# 555-PWM-Motor-Speed-Controller.net
KiCad netlist of a schematic drawn in EAGLE
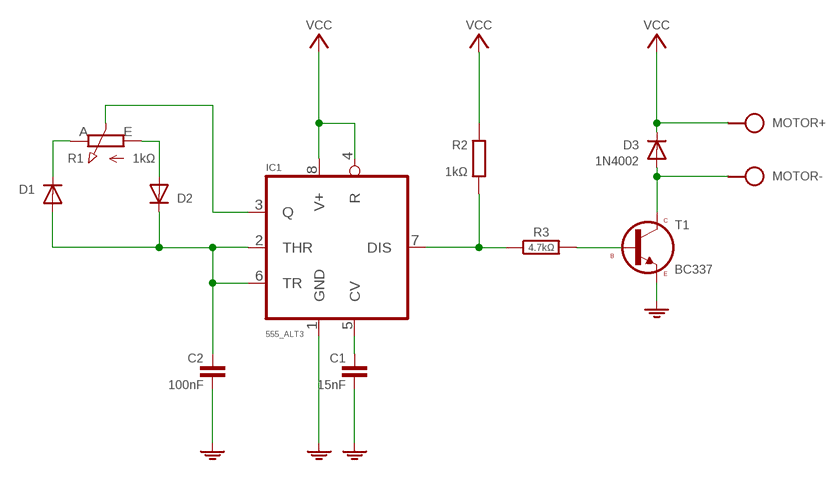
[diagram p0: schematic, sheet 1]

(export (version "E")
  (design (tool "Eeschema 10.0.6"))
  (components
    (comp (ref "C1")
      (value "15nF")
      (footprint "eagle-import:C050-020X044_V")
      (libsource (lib "eagle-import") (part "C050-020X044/V"))
    )
    (comp (ref "C2")
      (value "100nF")
      (footprint "eagle-import:C075-020X044")
      (libsource (lib "eagle-import") (part "C075-020X044"))
    )
    (comp (ref "D1")
      (value "DIODE34-7V")
      (footprint "eagle-import:DO34-7V")
      (libsource (lib "eagle-import") (part "DIODE34-7V"))
    )
    (comp (ref "D2")
      (value "DIODE34-7V")
      (footprint "eagle-import:DO34-7V")
      (libsource (lib "eagle-import") (part "DIODE34-7V"))
    )
    (comp (ref "D3")
      (value "1N4002")
      (footprint "eagle-import:DO35-7")
      (libsource (lib "eagle-import") (part "DIODE35-7"))
    )
    (comp (ref "IC1")
      (value "555_ALT3")
      (footprint "eagle-import:DIL08")
      (libsource (lib "eagle-import") (part "555_ALT3"))
    )
    (comp (ref "MOTOR")
      (value "SPAD+-+-")
      (footprint "eagle-import:SPAD+-")
      (libsource (lib "eagle-import") (part "SPAD+-+-"))
    )
    (comp (ref "R1")
      (value "1kΩ")
      (footprint "eagle-import:CONN-3P")
      (libsource (lib "eagle-import") (part "POT-H-3P"))
    )
    (comp (ref "R2")
      (value "1kΩ")
      (footprint "eagle-import:0204_10")
      (libsource (lib "eagle-import") (part "R0204/10"))
    )
    (comp (ref "R3")
      (value "4.7kΩ")
      (footprint "eagle-import:0204_10")
      (libsource (lib "eagle-import") (part "R-H0204/10"))
    )
    (comp (ref "S1")
      (value "VCC_GNDL")
      (footprint "eagle-import:SPAD-+")
      (libsource (lib "eagle-import") (part "VCC_GNDL"))
    )
    (comp (ref "T1")
      (value "BC337")
      (footprint "eagle-import:TO92-CBE-A")
      (libsource (lib "eagle-import") (part "BC337CBE-A"))
    )
  )
  (nets
    (net (code "1") (name "GND") (class "Default")
      (node (ref "C1") (pin "2") (pinfunction "2_2") (pintype "passive"))
      (node (ref "C2") (pin "2") (pinfunction "2_2") (pintype "passive"))
      (node (ref "IC1") (pin "1") (pinfunction "GND_1") (pintype "power_in"))
      (node (ref "S1") (pin "1") (pinfunction "GND_1") (pintype "power_in"))
      (node (ref "T1") (pin "3") (pinfunction "E_3") (pintype "passive"))
    )
    (net (code "2") (name "Net-(IC1-CV)") (class "Default")
      (node (ref "C1") (pin "1") (pinfunction "1_1") (pintype "passive"))
      (node (ref "IC1") (pin "5") (pinfunction "CV_5") (pintype "input"))
    )
    (net (code "3") (name "Net-(IC1-DIS)") (class "Default")
      (node (ref "IC1") (pin "7") (pinfunction "DIS_7") (pintype "passive"))
      (node (ref "R2") (pin "2") (pinfunction "1_2") (pintype "passive"))
      (node (ref "R3") (pin "1") (pinfunction "1_1") (pintype "passive"))
    )
    (net (code "4") (name "Net-(IC1-Q)") (class "Default")
      (node (ref "IC1") (pin "3") (pinfunction "Q_3") (pintype "output"))
      (node (ref "R1") (pin "2") (pinfunction "S_2") (pintype "passive"))
    )
    (net (code "5") (name "Net-(IC1-THR)") (class "Default")
      (node (ref "C2") (pin "1") (pinfunction "1_1") (pintype "passive"))
      (node (ref "D1") (pin "A") (pinfunction "A_A") (pintype "passive"))
      (node (ref "D2") (pin "C") (pinfunction "C_C") (pintype "passive"))
      (node (ref "IC1") (pin "2") (pinfunction "THR_2") (pintype "input"))
      (node (ref "IC1") (pin "6") (pinfunction "TR_6") (pintype "input"))
    )
    (net (code "6") (name "Net-(MOTORB-P$1)") (class "Default")
      (node (ref "D3") (pin "A") (pinfunction "A_A") (pintype "passive"))
      (node (ref "MOTOR") (pin "1") (pinfunction "P$1_1") (pintype "passive"))
      (node (ref "T1") (pin "1") (pinfunction "C_1") (pintype "passive"))
    )
    (net (code "7") (name "Net-(R1-A)") (class "Default")
      (node (ref "D2") (pin "A") (pinfunction "A_A") (pintype "passive"))
      (node (ref "R1") (pin "1") (pinfunction "A_1") (pintype "passive"))
    )
    (net (code "8") (name "Net-(R1-E)") (class "Default")
      (node (ref "D1") (pin "C") (pinfunction "C_C") (pintype "passive"))
      (node (ref "R1") (pin "3") (pinfunction "E_3") (pintype "passive"))
    )
    (net (code "9") (name "Net-(T1-B)") (class "Default")
      (node (ref "R3") (pin "2") (pinfunction "2_2") (pintype "passive"))
      (node (ref "T1") (pin "2") (pinfunction "B_2") (pintype "passive"))
    )
    (net (code "10") (name "VCC") (class "Default")
      (node (ref "D3") (pin "C") (pinfunction "C_C") (pintype "passive"))
      (node (ref "IC1") (pin "4") (pinfunction "R_4") (pintype "input"))
      (node (ref "IC1") (pin "8") (pinfunction "V+_8") (pintype "power_in"))
      (node (ref "MOTOR") (pin "2") (pinfunction "P$1_2") (pintype "passive"))
      (node (ref "R2") (pin "1") (pinfunction "2_1") (pintype "passive"))
      (node (ref "S1") (pin "2") (pinfunction "VCC_2") (pintype "power_in"))
    )
  )
)
